# PowerPCB_180.net
KiCad netlist of a schematic drawn in EAGLE
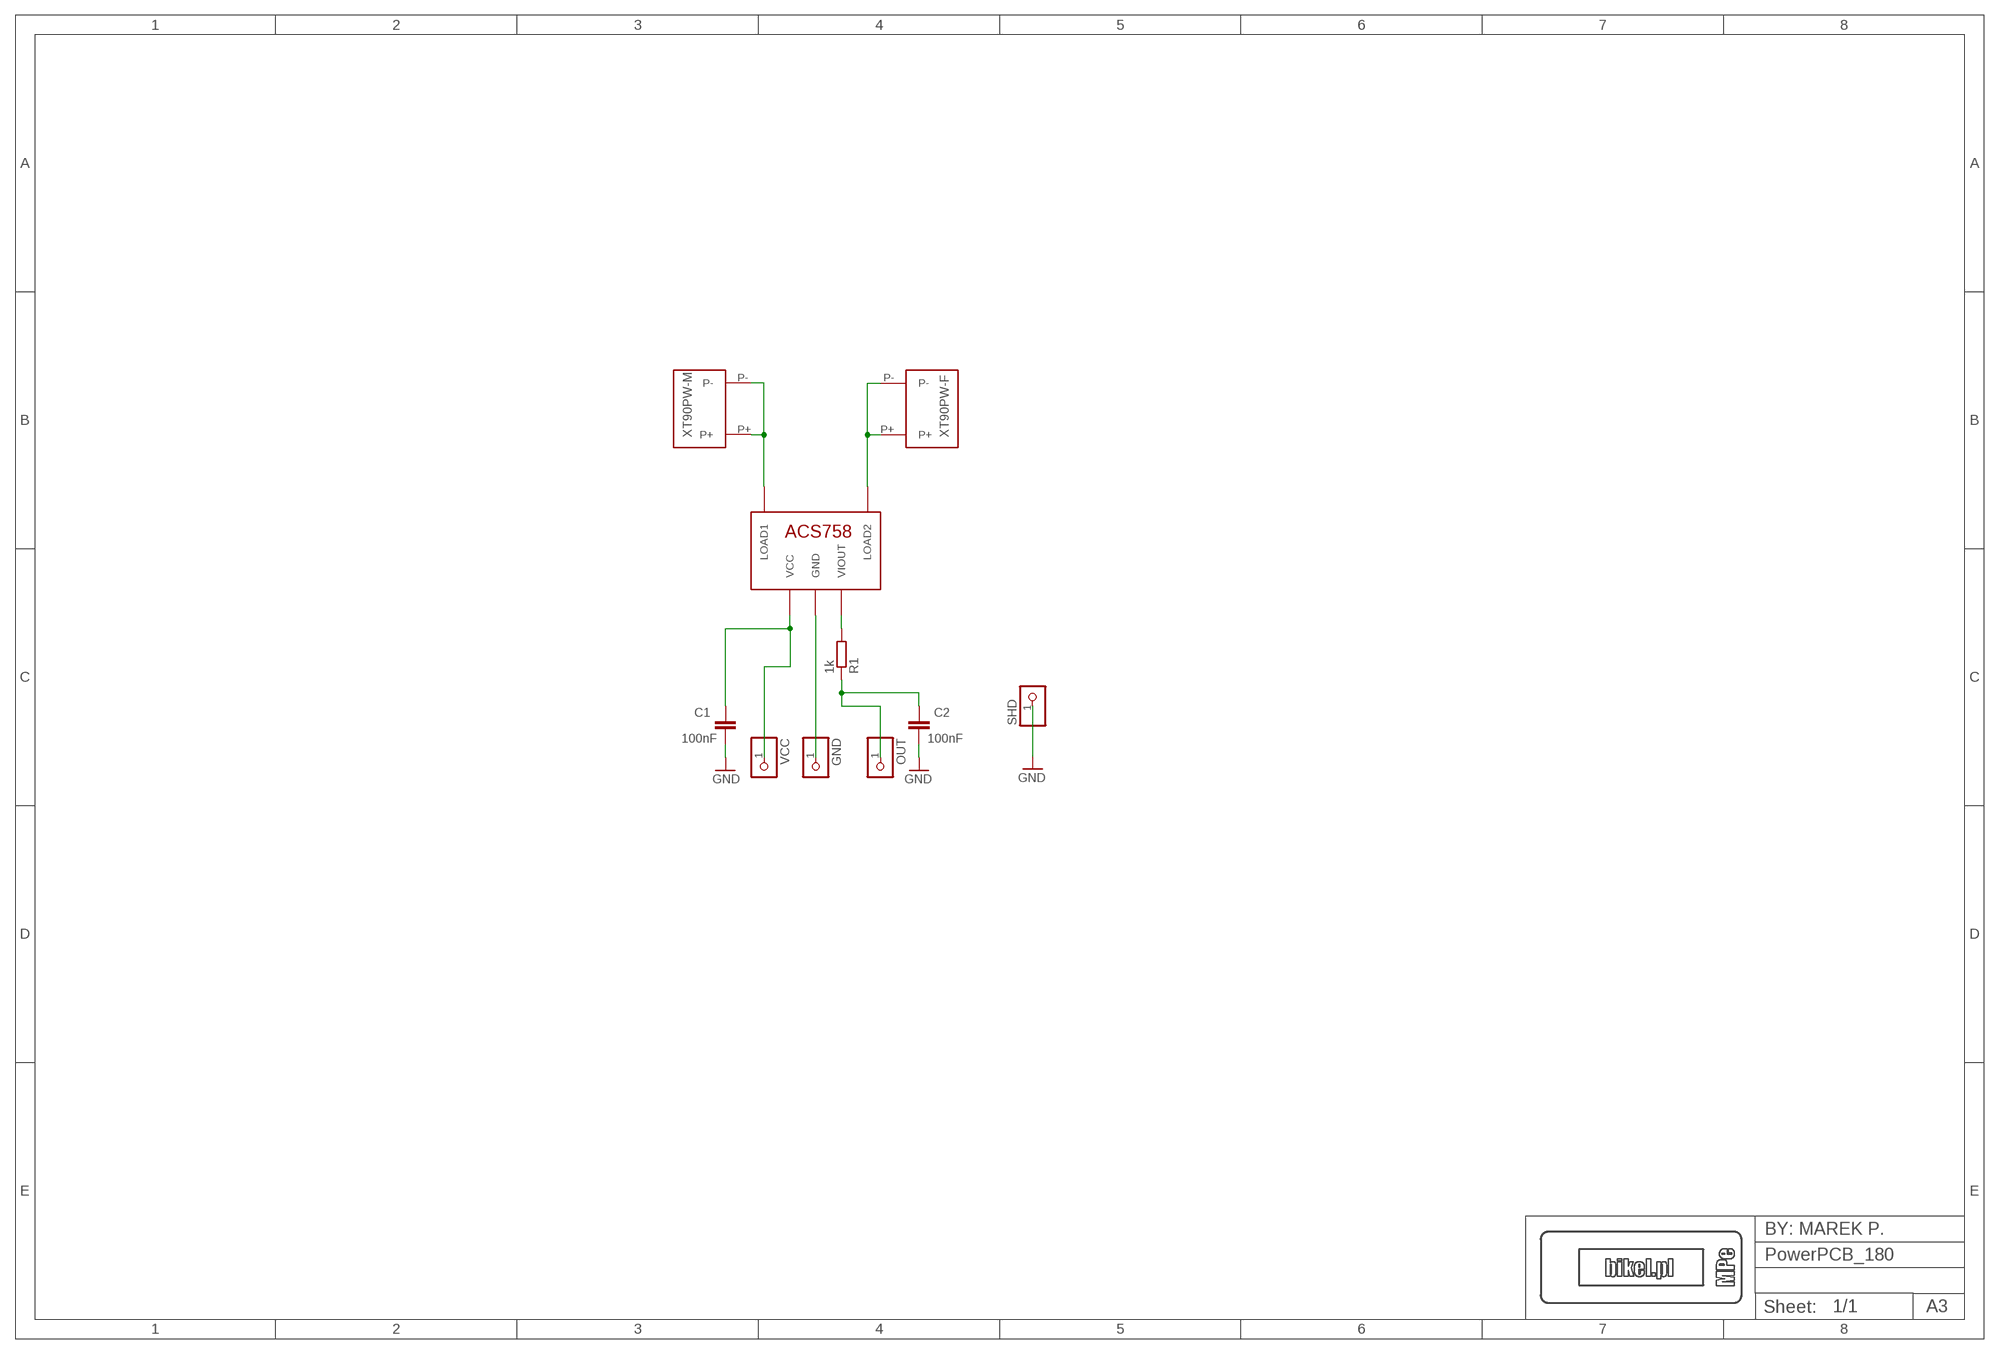
[diagram p0: schematic, sheet 1]

(export (version "E")
  (design (tool "Eeschema 10.0.6"))
  (components
    (comp (ref "ACS758_1")
      (value "ACS758")
      (footprint "eagle-import:ACS758-PFF")
      (libsource (lib "eagle-import") (part "ACS758"))
    )
    (comp (ref "C1")
      (value "100nF")
      (footprint "eagle-import:C0805")
      (libsource (lib "eagle-import") (part "C-EUC0805"))
    )
    (comp (ref "C2")
      (value "100nF")
      (footprint "eagle-import:C0805")
      (libsource (lib "eagle-import") (part "C-EUC0805"))
    )
    (comp (ref "GND")
      (value "PINHD-1X1")
      (footprint "eagle-import:1X01")
      (libsource (lib "eagle-import") (part "PINHD-1X1"))
    )
    (comp (ref "OUT")
      (value "PINHD-1X1")
      (footprint "eagle-import:1X01")
      (libsource (lib "eagle-import") (part "PINHD-1X1"))
    )
    (comp (ref "R1")
      (value "1k")
      (footprint "eagle-import:R0805")
      (libsource (lib "eagle-import") (part "R-EU_R0805"))
    )
    (comp (ref "SHD")
      (value "PINHD-1X1")
      (footprint "eagle-import:1X01")
      (libsource (lib "eagle-import") (part "PINHD-1X1"))
    )
    (comp (ref "VCC")
      (value "PINHD-1X1")
      (footprint "eagle-import:1X01")
      (libsource (lib "eagle-import") (part "PINHD-1X1"))
    )
    (comp (ref "XT90PW-F1")
      (value "XT90PW-F")
      (footprint "eagle-import:XT90PW-F")
      (libsource (lib "eagle-import") (part "XT90PW-F"))
    )
    (comp (ref "XT90PW-M1")
      (value "XT90PW-M")
      (footprint "eagle-import:XT90PW-M")
      (libsource (lib "eagle-import") (part "XT90PW-M"))
    )
  )
  (nets
    (net (code "1") (name "GND") (class "Default")
      (node (ref "ACS758_1") (pin "GND") (pinfunction "GND_GND") (pintype "bidirectional"))
      (node (ref "C1") (pin "2") (pinfunction "2_2") (pintype "passive"))
      (node (ref "C2") (pin "2") (pinfunction "2_2") (pintype "passive"))
      (node (ref "GND") (pin "1") (pinfunction "1_1") (pintype "passive"))
      (node (ref "SHD") (pin "1") (pinfunction "1_1") (pintype "passive"))
    )
    (net (code "2") (name "Net-(ACS758_1-PadLOAD1)") (class "Default")
      (node (ref "ACS758_1") (pin "LOAD1") (pinfunction "LOAD1_LOAD1") (pintype "bidirectional"))
      (node (ref "XT90PW-M1") (pin "P+") (pinfunction "P+_P+") (pintype "bidirectional"))
      (node (ref "XT90PW-M1") (pin "P-") (pinfunction "P-_P-") (pintype "bidirectional"))
    )
    (net (code "3") (name "Net-(ACS758_1-PadLOAD2)") (class "Default")
      (node (ref "ACS758_1") (pin "LOAD2") (pinfunction "LOAD2_LOAD2") (pintype "bidirectional"))
      (node (ref "XT90PW-F1") (pin "P+") (pinfunction "P+_P+") (pintype "bidirectional"))
      (node (ref "XT90PW-F1") (pin "P-") (pinfunction "P-_P-") (pintype "bidirectional"))
    )
    (net (code "4") (name "Net-(ACS758_1-PadVCC)") (class "Default")
      (node (ref "ACS758_1") (pin "VCC") (pinfunction "VCC_VCC") (pintype "bidirectional"))
      (node (ref "C1") (pin "1") (pinfunction "1_1") (pintype "passive"))
      (node (ref "VCC") (pin "1") (pinfunction "1_1") (pintype "passive"))
    )
    (net (code "5") (name "Net-(ACS758_1-PadVIOUT)") (class "Default")
      (node (ref "ACS758_1") (pin "VIOUT") (pinfunction "VIOUT_VIOUT") (pintype "bidirectional"))
      (node (ref "R1") (pin "2") (pinfunction "2_2") (pintype "passive"))
    )
    (net (code "6") (name "Net-(C2-Pad1)") (class "Default")
      (node (ref "C2") (pin "1") (pinfunction "1_1") (pintype "passive"))
      (node (ref "OUT") (pin "1") (pinfunction "1_1") (pintype "passive"))
      (node (ref "R1") (pin "1") (pinfunction "1_1") (pintype "passive"))
    )
  )
)
